# Poactuator_Circuits2.net
KiCad netlist of a schematic drawn in Altium Designer
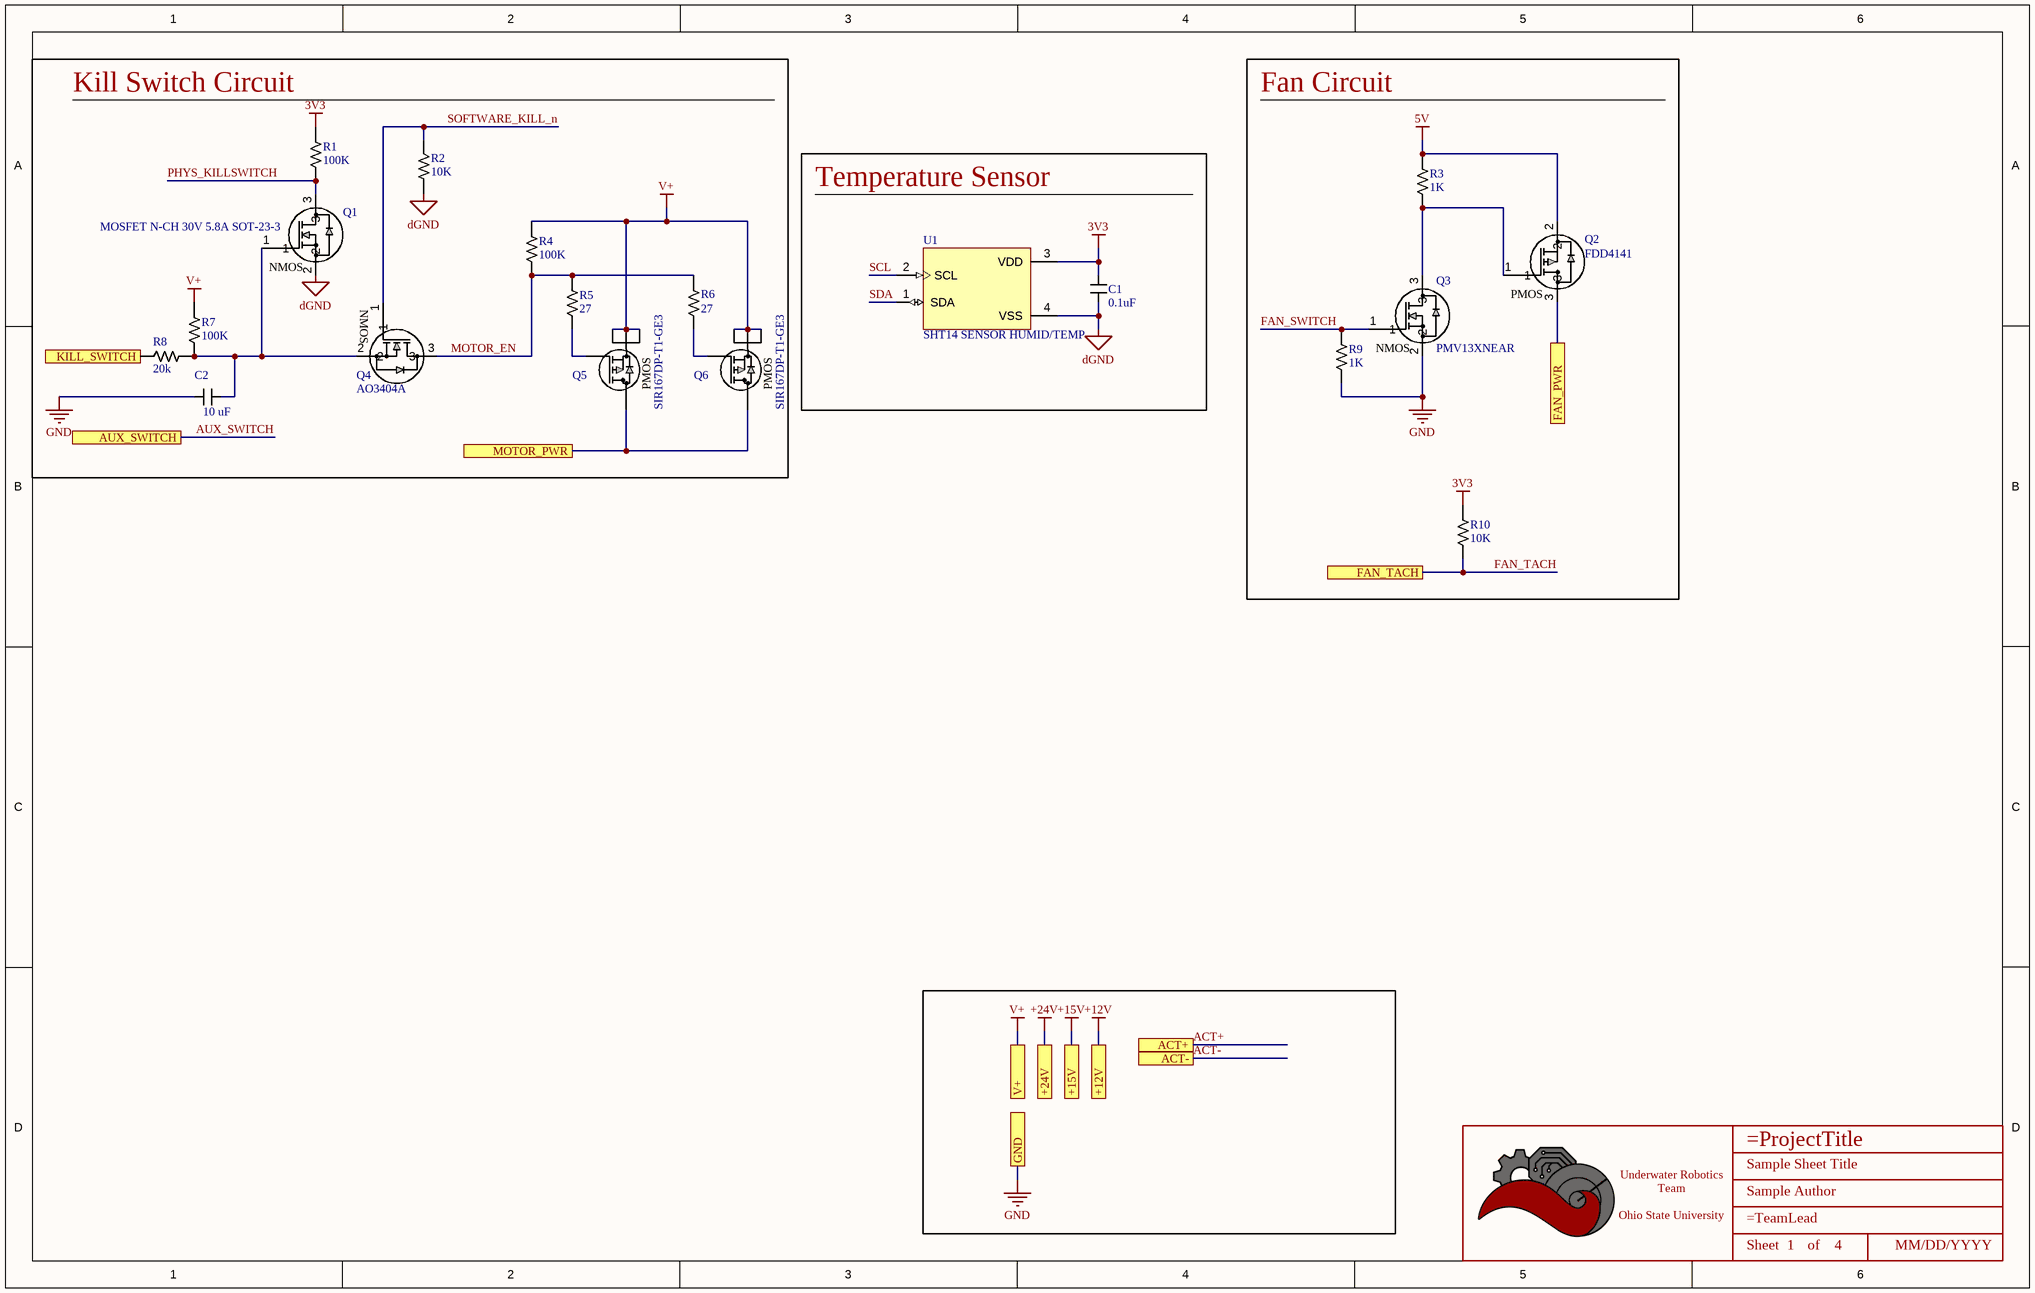
[diagram p0: Poactuator_Circuits2.SchDoc]

(export (version "E")
  (design (tool "Eeschema 10.0.6"))
  (components
    (comp (ref "*")
      (value "Title_Block")
      (footprint "LOGO")
      (description "UWRT Schematic Title Block Template\r\n\r\nCreated June 2021, Dylan Trainor")
      (libsource (lib "UWRT") (part "Title_Block"))
    )
    (comp (ref "C1")
      (value "0.1uF")
      (footprint "CAPACITOR_0603")
      (description "Cap 100nF 6.3V +/-10%\r\nCeramic 0603")
      (fields
        (field (name "TOLERANCE") "+/- 10%")
        (field (name "VOLTAGE") "6.3V")
        (field (name "MADE BY") "Flip B")
      )
      (libsource (lib "Capacitors") (part "CAPACITOR_0.1uF_0603"))
    )
    (comp (ref "C2")
      (value "10uF Ceramic 25V")
      (footprint "CAPACITOR_1206")
      (description "Cap 10uF 25V +/-10%\r\nCeramic 1206")
      (fields
        (field (name "TOLERANCE") "+/- 10%")
        (field (name "VOLTAGE") "25V")
        (field (name "VALUE (UF)") "10 uF")
        (field (name "MADE BY") "Robert Pafford")
      )
      (libsource (lib "Capacitors") (part "CAPACITOR_10uF_1206"))
    )
    (comp (ref "Q1")
      (value "MOSFET N-CH 30V 5.8A SOT-23-3")
      (footprint "SOT-23-3")
      (description "N-Channel 30 V 5.8A (Ta) 1.4W (Ta) Surface Mount SOT-23-3")
      (fields (field (name "MANUFACTURER _PART_NUMBER") "AO3404A") (field (name "CREATED BY") "Dylan T"))
      (libsource (lib "Transistors") (part "AO3404A"))
    )
    (comp (ref "Q2")
      (value "FDD4141")
      (footprint "DPAK_ONS")
      (description "P-Channel 10.8A (Ta), 50A (Tc) 2.4W (Ta), 69W (Tc) Surface Mount D-PAK (TO-252AA)")
      (fields (field (name "CREATED BY") "Dylan T"))
      (libsource (lib "Transistors") (part "FDD4141"))
    )
    (comp (ref "Q3")
      (value "PMV13XNEAR")
      (footprint "SOT-23-3")
      (description "N-Channel 20 V 7.3A (Ta) 610mW (Ta), 8.3W (Tc) Surface Mount TO-236AB")
      (fields (field (name "CREATED BY") "Dylan T"))
      (libsource (lib "Transistors") (part "PMV13XNEAR"))
    )
    (comp (ref "Q4")
      (value "AO3404A")
      (footprint "SOT-23-3")
      (description "N-Channel 30 V 5.8A (Ta) 1.4W (Ta) Surface Mount SOT-23-3")
      (fields (field (name "CREATED BY") "Dylan T"))
      (libsource (lib "Transistors") (part "AO3404A"))
    )
    (comp (ref "Q5")
      (value "SIR167DP-T1-GE3")
      (footprint "MOSFET_7DP-T1-GE3_VIS")
      (description "P-Channel 30 V 60A (Tc) 65.8W (Tc) Surface Mount PowerPAK® SO-8")
      (fields (field (name "COPYRIGHT") "Copyright (C) 2022 Ultra Librarian. All rights reserved."))
      (libsource (lib "Transistors") (part "SIR167DP-T1-GE3"))
    )
    (comp (ref "Q6")
      (value "SIR167DP-T1-GE3")
      (footprint "MOSFET_7DP-T1-GE3_VIS")
      (description "P-Channel 30 V 60A (Tc) 65.8W (Tc) Surface Mount PowerPAK® SO-8")
      (fields (field (name "COPYRIGHT") "Copyright (C) 2022 Ultra Librarian. All rights reserved."))
      (libsource (lib "Transistors") (part "SIR167DP-T1-GE3"))
    )
    (comp (ref "R1")
      (value "100k Ohm 0.5% 1/10W")
      (footprint "RESISTOR_0603")
      (description "RES 100k OHM 0.5% 1/10W 0603")
      (fields
        (field (name "TOLERANCE") "+/- 0.5%")
        (field (name "VALUE  (OHMS)") "100K")
        (field (name "MADE BY") "John Ulm")
      )
      (libsource (lib "Resistors") (part "RESISTOR_100K_0.5%_0603"))
    )
    (comp (ref "R2")
      (value "10k Ohm 5% 1/10W")
      (footprint "RESISTOR_0603")
      (description "RES 10k OHM 5% 1/10W 0603")
      (fields
        (field (name "TOLERANCE") "+/- 5%")
        (field (name "VALUE  (OHMS)") "10K")
        (field (name "MADE BY") "Robert Pafford")
      )
      (libsource (lib "Resistors") (part "RESISTOR_10K_0603"))
    )
    (comp (ref "R3")
      (value "1k Ohm 5% 1/8W")
      (footprint "RESISTOR_0603")
      (description "RES 1k OHM 5% 1/8W 0603")
      (fields
        (field (name "TOLERANCE") "+/- 5%")
        (field (name "VALUE  (OHMS)") "1K")
        (field (name "MADE BY") "Robert Pafford")
      )
      (libsource (lib "Resistors") (part "RESISTOR_1K_0603"))
    )
    (comp (ref "R4")
      (value "100k Ohm 0.5% 1/10W")
      (footprint "RESISTOR_0603")
      (description "RES 100k OHM 0.5% 1/10W 0603")
      (fields
        (field (name "TOLERANCE") "+/- 0.5%")
        (field (name "VALUE  (OHMS)") "100K")
        (field (name "MADE BY") "John Ulm")
      )
      (libsource (lib "Resistors") (part "RESISTOR_100K_0.5%_0603"))
    )
    (comp (ref "R5")
      (value "27 Ohm 5% 1/8W")
      (footprint "RESISTOR_0603")
      (description "RES 27 OHM 5% 1/8W 0603")
      (fields
        (field (name "TOLERANCE") "+/- 5%")
        (field (name "VALUE  (OHMS)") "27")
        (field (name "MADE BY") "Robert Pafford")
      )
      (libsource (lib "Resistors") (part "RESISTOR_27_0603"))
    )
    (comp (ref "R6")
      (value "27 Ohm 5% 1/8W")
      (footprint "RESISTOR_0603")
      (description "RES 27 OHM 5% 1/8W 0603")
      (fields
        (field (name "TOLERANCE") "+/- 5%")
        (field (name "VALUE  (OHMS)") "27")
        (field (name "MADE BY") "Robert Pafford")
      )
      (libsource (lib "Resistors") (part "RESISTOR_27_0603"))
    )
    (comp (ref "R7")
      (value "100k Ohm 0.5% 1/10W")
      (footprint "RESISTOR_0603")
      (description "RES 100k OHM 0.5% 1/10W 0603")
      (fields
        (field (name "TOLERANCE") "+/- 0.5%")
        (field (name "VALUE  (OHMS)") "100K")
        (field (name "MADE BY") "John Ulm")
      )
      (libsource (lib "Resistors") (part "RESISTOR_100K_0.5%_0603"))
    )
    (comp (ref "R8")
      (value "20k Ohm 1% 1/16W")
      (footprint "RESISTOR_0402")
      (description "RES 20k OHM 1% 1/16W 0402")
      (fields
        (field (name "TOLERANCE") "+/- 1%")
        (field (name "VALUE  (OHMS)") "20k")
        (field (name "MADE BY") "Flip B")
      )
      (libsource (lib "Resistors") (part "RESISTOR_20K_0402"))
    )
    (comp (ref "R9")
      (value "1k Ohm 5% 1/8W")
      (footprint "RESISTOR_0603")
      (description "RES 1k OHM 5% 1/8W 0603")
      (fields
        (field (name "TOLERANCE") "+/- 5%")
        (field (name "VALUE  (OHMS)") "1K")
        (field (name "MADE BY") "Robert Pafford")
      )
      (libsource (lib "Resistors") (part "RESISTOR_1K_0603"))
    )
    (comp (ref "R10")
      (value "10k Ohm 5% 1/10W")
      (footprint "RESISTOR_0603")
      (description "RES 10k OHM 5% 1/10W 0603")
      (fields
        (field (name "TOLERANCE") "+/- 5%")
        (field (name "VALUE  (OHMS)") "10K")
        (field (name "MADE BY") "Robert Pafford")
      )
      (libsource (lib "Resistors") (part "RESISTOR_10K_0603"))
    )
    (comp (ref "U1")
      (value "SHT14 SENSOR HUMID/TEMP")
      (footprint "XDCR_SHT41-AD1B-R2")
      (description "Digital Relative Humidity Temperature Sensor, Â±1.8 / max 2.5 %RH, Â±0.2 Â°C, Ultra-Low-Power")
      (fields (field (name "MP") "SHT41-AD1B-R2") (field (name "MF") "Sensirion"))
      (libsource (lib "Integrated Circuits") (part "SHT41-AD1B-R2"))
    )
  )
  (nets
    (net (code "7") (name "/FAN_PWR") (class "Default")
      (node (ref "Q2") (pin "3") (pinfunction "3_3") (pintype "passive"))
    )
    (net (code "8") (name "/FAN_SWITCH") (class "Default")
      (node (ref "Q3") (pin "1") (pinfunction "1_1") (pintype "passive"))
      (node (ref "R9") (pin "1") (pinfunction "1_1") (pintype "passive"))
    )
    (net (code "9") (name "/FAN_TACH") (class "Default")
      (node (ref "R10") (pin "2") (pinfunction "2_2") (pintype "passive"))
    )
    (net (code "10") (name "/KILL_SWITCH") (class "Default")
      (node (ref "R8") (pin "2") (pinfunction "2_2") (pintype "passive"))
    )
    (net (code "11") (name "/MOTOR_EN") (class "Default")
      (node (ref "Q4") (pin "3") (pinfunction "3_3") (pintype "passive"))
      (node (ref "R4") (pin "2") (pinfunction "2_2") (pintype "passive"))
      (node (ref "R5") (pin "1") (pinfunction "1_1") (pintype "passive"))
      (node (ref "R6") (pin "1") (pinfunction "1_1") (pintype "passive"))
    )
    (net (code "12") (name "/MOTOR_PWR") (class "Default")
      (node (ref "Q5") (pin "D") (pinfunction "D_D") (pintype "passive"))
      (node (ref "Q6") (pin "D") (pinfunction "D_D") (pintype "passive"))
    )
    (net (code "13") (name "/PHYS_KILLSWITCH") (class "Default")
      (node (ref "Q1") (pin "3") (pinfunction "3_3") (pintype "passive"))
      (node (ref "R1") (pin "2") (pinfunction "2_2") (pintype "passive"))
    )
    (net (code "14") (name "/SCL") (class "Default")
      (node (ref "U1") (pin "2") (pinfunction "SCL_2") (pintype "input"))
    )
    (net (code "15") (name "/SDA") (class "Default")
      (node (ref "U1") (pin "1") (pinfunction "SDA_1") (pintype "bidirectional"))
    )
    (net (code "16") (name "/SOFTWARE_KILL_n") (class "Default")
      (node (ref "Q4") (pin "1") (pinfunction "1_1") (pintype "passive"))
      (node (ref "R2") (pin "2") (pinfunction "2_2") (pintype "passive"))
    )
    (net (code "17") (name "3V3") (class "Default")
      (node (ref "C1") (pin "1") (pinfunction "1_1") (pintype "passive"))
      (node (ref "R1") (pin "1") (pinfunction "1_1") (pintype "passive"))
      (node (ref "R10") (pin "1") (pinfunction "1_1") (pintype "passive"))
      (node (ref "U1") (pin "3") (pinfunction "VDD_3") (pintype "power_in"))
    )
    (net (code "18") (name "5V") (class "Default")
      (node (ref "Q2") (pin "2") (pinfunction "2_2") (pintype "passive"))
      (node (ref "R3") (pin "1") (pinfunction "1_1") (pintype "passive"))
    )
    (net (code "19") (name "GND") (class "Default")
      (node (ref "C2") (pin "2") (pinfunction "2_2") (pintype "passive"))
      (node (ref "Q3") (pin "2") (pinfunction "2_2") (pintype "passive"))
      (node (ref "R9") (pin "2") (pinfunction "2_2") (pintype "passive"))
    )
    (net (code "20") (name "Net-(C2-Pad1)") (class "Default")
      (node (ref "C2") (pin "1") (pinfunction "1_1") (pintype "passive"))
      (node (ref "Q1") (pin "1") (pinfunction "1_1") (pintype "passive"))
      (node (ref "Q4") (pin "2") (pinfunction "2_2") (pintype "passive"))
      (node (ref "R7") (pin "2") (pinfunction "2_2") (pintype "passive"))
      (node (ref "R8") (pin "1") (pinfunction "1_1") (pintype "passive"))
    )
    (net (code "21") (name "Net-(Q2-Pad1)") (class "Default")
      (node (ref "Q2") (pin "1") (pinfunction "1_1") (pintype "passive"))
      (node (ref "Q3") (pin "3") (pinfunction "3_3") (pintype "passive"))
      (node (ref "R3") (pin "2") (pinfunction "2_2") (pintype "passive"))
    )
    (net (code "22") (name "Net-(Q5-G)") (class "Default")
      (node (ref "Q5") (pin "4") (pinfunction "G_4") (pintype "passive"))
      (node (ref "R5") (pin "2") (pinfunction "2_2") (pintype "passive"))
    )
    (net (code "23") (name "Net-(Q6-G)") (class "Default")
      (node (ref "Q6") (pin "4") (pinfunction "G_4") (pintype "passive"))
      (node (ref "R6") (pin "2") (pinfunction "2_2") (pintype "passive"))
    )
    (net (code "24") (name "V+") (class "Default")
      (node (ref "Q5") (pin "1") (pinfunction "S_1") (pintype "passive"))
      (node (ref "Q5") (pin "2") (pinfunction "S_2") (pintype "passive"))
      (node (ref "Q5") (pin "3") (pinfunction "S_3") (pintype "passive"))
      (node (ref "Q6") (pin "1") (pinfunction "S_1") (pintype "passive"))
      (node (ref "Q6") (pin "2") (pinfunction "S_2") (pintype "passive"))
      (node (ref "Q6") (pin "3") (pinfunction "S_3") (pintype "passive"))
      (node (ref "R4") (pin "1") (pinfunction "1_1") (pintype "passive"))
      (node (ref "R7") (pin "1") (pinfunction "1_1") (pintype "passive"))
    )
    (net (code "25") (name "dGND") (class "Default")
      (node (ref "C1") (pin "2") (pinfunction "2_2") (pintype "passive"))
      (node (ref "Q1") (pin "2") (pinfunction "2_2") (pintype "passive"))
      (node (ref "R2") (pin "1") (pinfunction "1_1") (pintype "passive"))
      (node (ref "U1") (pin "4") (pinfunction "VSS_4") (pintype "power_in"))
    )
  )
)
